# Controller.net
KiCad netlist of a schematic drawn in Altium Designer
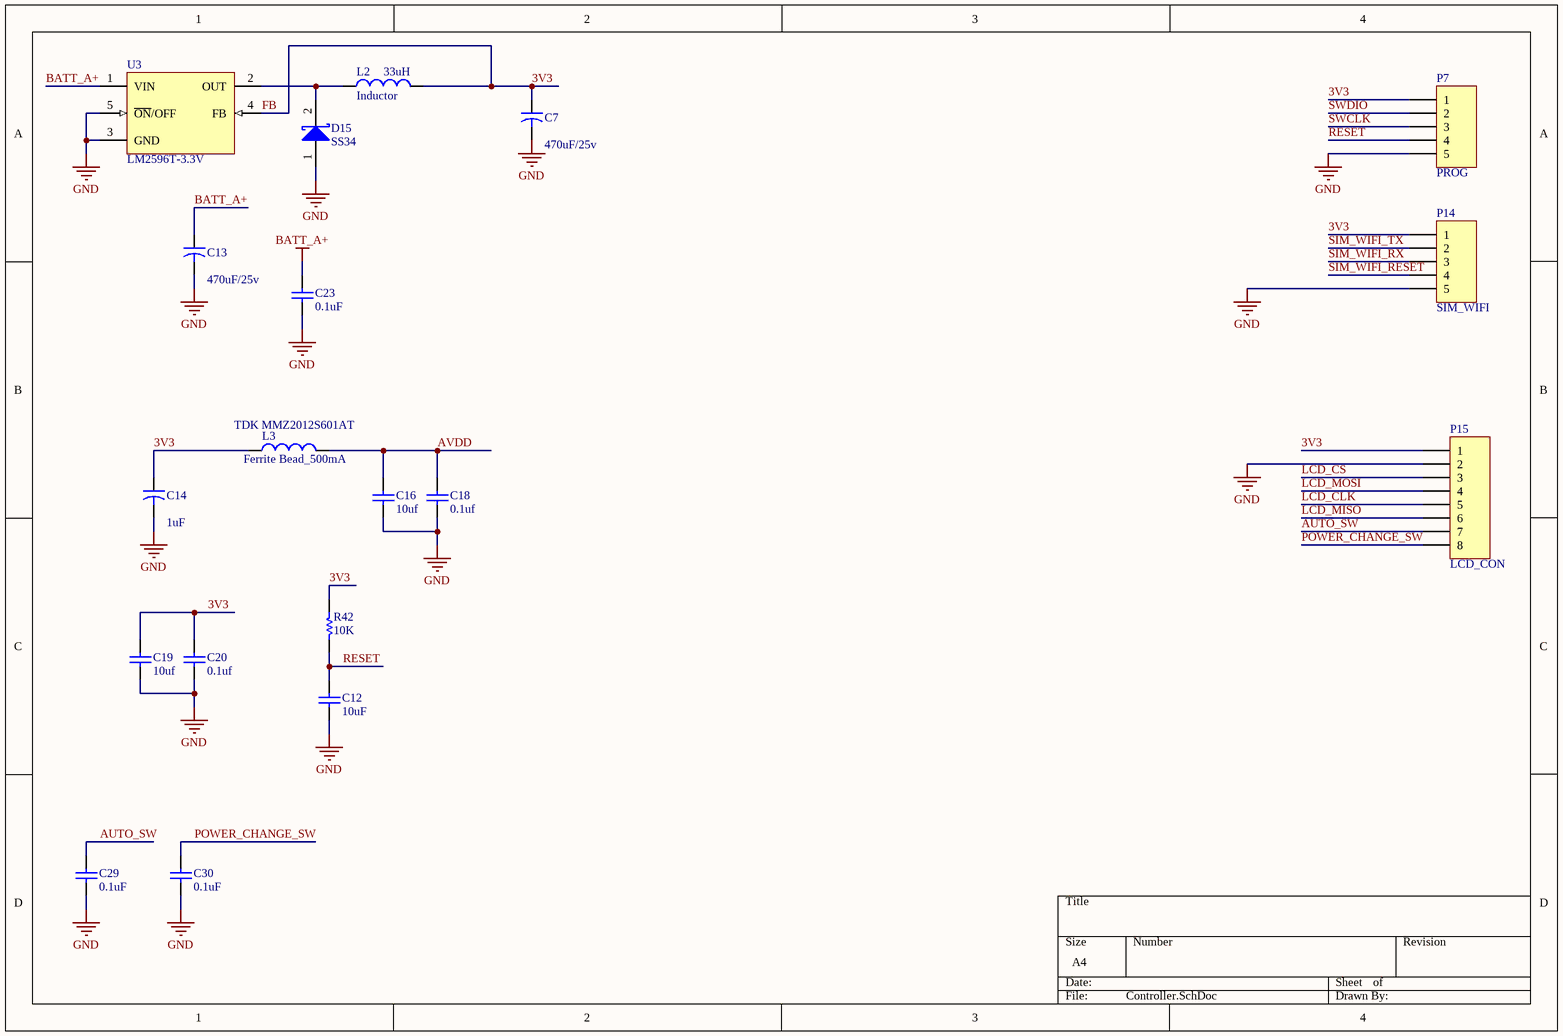
[diagram p0: Controller.SchDoc]

(export (version "E")
  (design (tool "Eeschema 10.0.6"))
  (components
    (comp (ref "C7")
      (value "470uF/25v")
      (footprint "Cap_470uf_10X10.2mm")
      (description "Capacitor")
      (fields (field (name "Comment") "Cap2") (field (name "PUBLISHER") "Altium Limited"))
      (libsource (lib "Miscellaneous Devices") (part "Cap2"))
    )
    (comp (ref "C12")
      (value "10uF")
      (footprint "0805")
      (description "Capacitor")
      (fields (field (name "Comment") "Cap") (field (name "PUBLISHER") "Altium Limited"))
      (libsource (lib "Miscellaneous Devices") (part "Cap"))
    )
    (comp (ref "C13")
      (value "470uF/25v")
      (footprint "Cap_470uf_10X10.2mm")
      (description "Capacitor")
      (fields (field (name "Comment") "Cap2") (field (name "PUBLISHER") "Altium Limited"))
      (libsource (lib "Miscellaneous Devices") (part "Cap2"))
    )
    (comp (ref "C14")
      (value "1uF")
      (footprint "0805")
      (description "Capacitor")
      (fields (field (name "Comment") "Cap2") (field (name "PUBLISHER") "Altium Limited"))
      (libsource (lib "Miscellaneous Devices") (part "Cap2"))
    )
    (comp (ref "C16")
      (value "10uf")
      (footprint "0805")
      (description "Capacitor")
      (fields (field (name "Comment") "Cap") (field (name "PUBLISHER") "Altium Limited"))
      (libsource (lib "Miscellaneous Devices") (part "Cap"))
    )
    (comp (ref "C18")
      (value "0.1uf")
      (footprint "0805")
      (description "Capacitor")
      (fields (field (name "Comment") "Cap") (field (name "PUBLISHER") "Altium Limited"))
      (libsource (lib "Miscellaneous Devices") (part "Cap"))
    )
    (comp (ref "C19")
      (value "10uf")
      (footprint "0805")
      (description "Capacitor")
      (fields (field (name "Comment") "Cap") (field (name "PUBLISHER") "Altium Limited"))
      (libsource (lib "Miscellaneous Devices") (part "Cap"))
    )
    (comp (ref "C20")
      (value "0.1uf")
      (footprint "SMDlibrary:0805")
      (description "Capacitor")
      (fields (field (name "Comment") "Cap") (field (name "PUBLISHER") "Altium Limited"))
      (libsource (lib "Miscellaneous Devices") (part "Cap"))
    )
    (comp (ref "C23")
      (value "0.1uF")
      (footprint "0805")
      (description "Capacitor")
      (fields (field (name "Comment") "Cap") (field (name "PUBLISHER") "Altium Limited"))
      (libsource (lib "Miscellaneous Devices") (part "Cap"))
    )
    (comp (ref "C29")
      (value "0.1uF")
      (footprint "0805")
      (description "Capacitor")
      (fields (field (name "Comment") "Cap") (field (name "PUBLISHER") "Altium Limited"))
      (libsource (lib "Miscellaneous Devices") (part "Cap"))
    )
    (comp (ref "C30")
      (value "0.1uF")
      (footprint "0805")
      (description "Capacitor")
      (fields (field (name "Comment") "Cap") (field (name "PUBLISHER") "Altium Limited"))
      (libsource (lib "Miscellaneous Devices") (part "Cap"))
    )
    (comp (ref "D15")
      (value "SS34")
      (footprint "SMDlibrary:SMA")
      (description "Schottky Rectifier")
      (fields (field (name "PUBLISHER") "Altium Limited"))
      (libsource (lib "Miscellaneous Devices") (part "Diode 10TQ035"))
    )
    (comp (ref "L2")
      (value "Inductor")
      (footprint "SMDlibrary:Inductor_SMD_33uh")
      (fields (field (name "ALTIUM_VALUE") "33uH") (field (name "PUBLISHER") "Altium Limited"))
      (libsource (lib "Miscellaneous Devices") (part "Inductor"))
    )
    (comp (ref "L3")
      (value "Ferrite Bead_500mA")
      (footprint "SMDlibrary:0805")
      (description "Inductor")
      (fields (field (name "ALTIUM_VALUE") "TDK MMZ2012S601AT") (field (name "PUBLISHER") "Altium Limited"))
      (libsource (lib "Miscellaneous Devices") (part "Inductor"))
    )
    (comp (ref "P7")
      (value "PROG")
      (footprint "HDR1X5")
      (description "Header, 5-Pin")
      (fields (field (name "PUBLISHER") "Altium Limited"))
      (libsource (lib "Miscellaneous Connectors") (part "Header 5"))
    )
    (comp (ref "P14")
      (value "SIM_WIFI")
      (footprint "HDR1X5")
      (description "Header, 5-Pin")
      (fields (field (name "PUBLISHER") "Altium Limited"))
      (libsource (lib "Miscellaneous Connectors") (part "Header 5"))
    )
    (comp (ref "P15")
      (value "LCD_CON")
      (footprint "HDR1X8")
      (description "Header, 8-Pin")
      (fields (field (name "PUBLISHER") "Altium Limited"))
      (libsource (lib "Miscellaneous Connectors") (part "Header 8"))
    )
    (comp (ref "R42")
      (value "10K")
      (footprint "0805")
      (description "Resistor")
      (fields (field (name "Comment") "Res1") (field (name "PUBLISHER") "Altium Limited"))
      (libsource (lib "Miscellaneous Devices") (part "Res1"))
    )
    (comp (ref "U3")
      (value "LM2596T-3.3V")
      (footprint "SMDlibrary:LM2596S50TR")
      (fields
        (field (name "PARTNUMBER") "LM2596T-3.3")
        (field (name "MANUFACTURER") "National Semiconductor")
      )
      (libsource (lib "SchLib") (part "LM2596T-ADJ"))
    )
  )
  (nets
    (net (code "1") (name "/3V3") (class "Default")
      (node (ref "C14") (pin "1") (pinfunction "1_1") (pintype "passive"))
      (node (ref "C19") (pin "2") (pinfunction "2_2") (pintype "passive"))
      (node (ref "C20") (pin "2") (pinfunction "2_2") (pintype "passive"))
      (node (ref "C7") (pin "1") (pinfunction "1_1") (pintype "passive"))
      (node (ref "L2") (pin "2") (pinfunction "2_2") (pintype "passive"))
      (node (ref "L3") (pin "1") (pinfunction "1_1") (pintype "passive"))
      (node (ref "P14") (pin "1") (pinfunction "1_1") (pintype "passive"))
      (node (ref "P15") (pin "1") (pinfunction "1_1") (pintype "passive"))
      (node (ref "P7") (pin "1") (pinfunction "1_1") (pintype "passive"))
      (node (ref "R42") (pin "1") (pinfunction "1_1") (pintype "passive"))
      (node (ref "U3") (pin "4") (pinfunction "FB_4") (pintype "input"))
    )
    (net (code "2") (name "/AUTO_SW") (class "Default")
      (node (ref "C29") (pin "1") (pinfunction "1_1") (pintype "passive"))
      (node (ref "P15") (pin "7") (pinfunction "7_7") (pintype "passive"))
    )
    (net (code "3") (name "/AVDD") (class "Default")
      (node (ref "C16") (pin "2") (pinfunction "2_2") (pintype "passive"))
      (node (ref "C18") (pin "2") (pinfunction "2_2") (pintype "passive"))
      (node (ref "L3") (pin "2") (pinfunction "2_2") (pintype "passive"))
    )
    (net (code "4") (name "/LCD_CLK") (class "Default")
      (node (ref "P15") (pin "5") (pinfunction "5_5") (pintype "passive"))
    )
    (net (code "5") (name "/LCD_CS") (class "Default")
      (node (ref "P15") (pin "3") (pinfunction "3_3") (pintype "passive"))
    )
    (net (code "6") (name "/LCD_MISO") (class "Default")
      (node (ref "P15") (pin "6") (pinfunction "6_6") (pintype "passive"))
    )
    (net (code "7") (name "/LCD_MOSI") (class "Default")
      (node (ref "P15") (pin "4") (pinfunction "4_4") (pintype "passive"))
    )
    (net (code "8") (name "/POWER_CHANGE_SW") (class "Default")
      (node (ref "C30") (pin "1") (pinfunction "1_1") (pintype "passive"))
      (node (ref "P15") (pin "8") (pinfunction "8_8") (pintype "passive"))
    )
    (net (code "9") (name "/RESET") (class "Default")
      (node (ref "C12") (pin "2") (pinfunction "2_2") (pintype "passive"))
      (node (ref "P7") (pin "4") (pinfunction "4_4") (pintype "passive"))
      (node (ref "R42") (pin "2") (pinfunction "2_2") (pintype "passive"))
    )
    (net (code "10") (name "/SIM_WIFI_RESET") (class "Default")
      (node (ref "P14") (pin "4") (pinfunction "4_4") (pintype "passive"))
    )
    (net (code "11") (name "/SIM_WIFI_RX") (class "Default")
      (node (ref "P14") (pin "3") (pinfunction "3_3") (pintype "passive"))
    )
    (net (code "12") (name "/SIM_WIFI_TX") (class "Default")
      (node (ref "P14") (pin "2") (pinfunction "2_2") (pintype "passive"))
    )
    (net (code "13") (name "/SWCLK") (class "Default")
      (node (ref "P7") (pin "3") (pinfunction "3_3") (pintype "passive"))
    )
    (net (code "14") (name "/SWDIO") (class "Default")
      (node (ref "P7") (pin "2") (pinfunction "2_2") (pintype "passive"))
    )
    (net (code "15") (name "BATT_A+") (class "Default")
      (node (ref "C13") (pin "1") (pinfunction "1_1") (pintype "passive"))
      (node (ref "C23") (pin "1") (pinfunction "1_1") (pintype "passive"))
      (node (ref "U3") (pin "1") (pinfunction "VIN_1") (pintype "power_in"))
    )
    (net (code "16") (name "GND") (class "Default")
      (node (ref "C12") (pin "1") (pinfunction "1_1") (pintype "passive"))
      (node (ref "C13") (pin "2") (pinfunction "2_2") (pintype "passive"))
      (node (ref "C14") (pin "2") (pinfunction "2_2") (pintype "passive"))
      (node (ref "C16") (pin "1") (pinfunction "1_1") (pintype "passive"))
      (node (ref "C18") (pin "1") (pinfunction "1_1") (pintype "passive"))
      (node (ref "C19") (pin "1") (pinfunction "1_1") (pintype "passive"))
      (node (ref "C20") (pin "1") (pinfunction "1_1") (pintype "passive"))
      (node (ref "C23") (pin "2") (pinfunction "2_2") (pintype "passive"))
      (node (ref "C29") (pin "2") (pinfunction "2_2") (pintype "passive"))
      (node (ref "C30") (pin "2") (pinfunction "2_2") (pintype "passive"))
      (node (ref "C7") (pin "2") (pinfunction "2_2") (pintype "passive"))
      (node (ref "D15") (pin "1") (pinfunction "A_1") (pintype "passive"))
      (node (ref "P14") (pin "5") (pinfunction "5_5") (pintype "passive"))
      (node (ref "P15") (pin "2") (pinfunction "2_2") (pintype "passive"))
      (node (ref "P7") (pin "5") (pinfunction "5_5") (pintype "passive"))
      (node (ref "U3") (pin "3") (pinfunction "GND_3") (pintype "power_in"))
      (node (ref "U3") (pin "5") (pinfunction "~{ON}/OFF_5") (pintype "input"))
    )
    (net (code "17") (name "Net-(D15-K)") (class "Default")
      (node (ref "D15") (pin "2") (pinfunction "K_2") (pintype "passive"))
      (node (ref "L2") (pin "1") (pinfunction "1_1") (pintype "passive"))
      (node (ref "U3") (pin "2") (pinfunction "OUT_2") (pintype "power_in"))
    )
  )
)
